# main.net
KiCad netlist of a schematic drawn in EAGLE
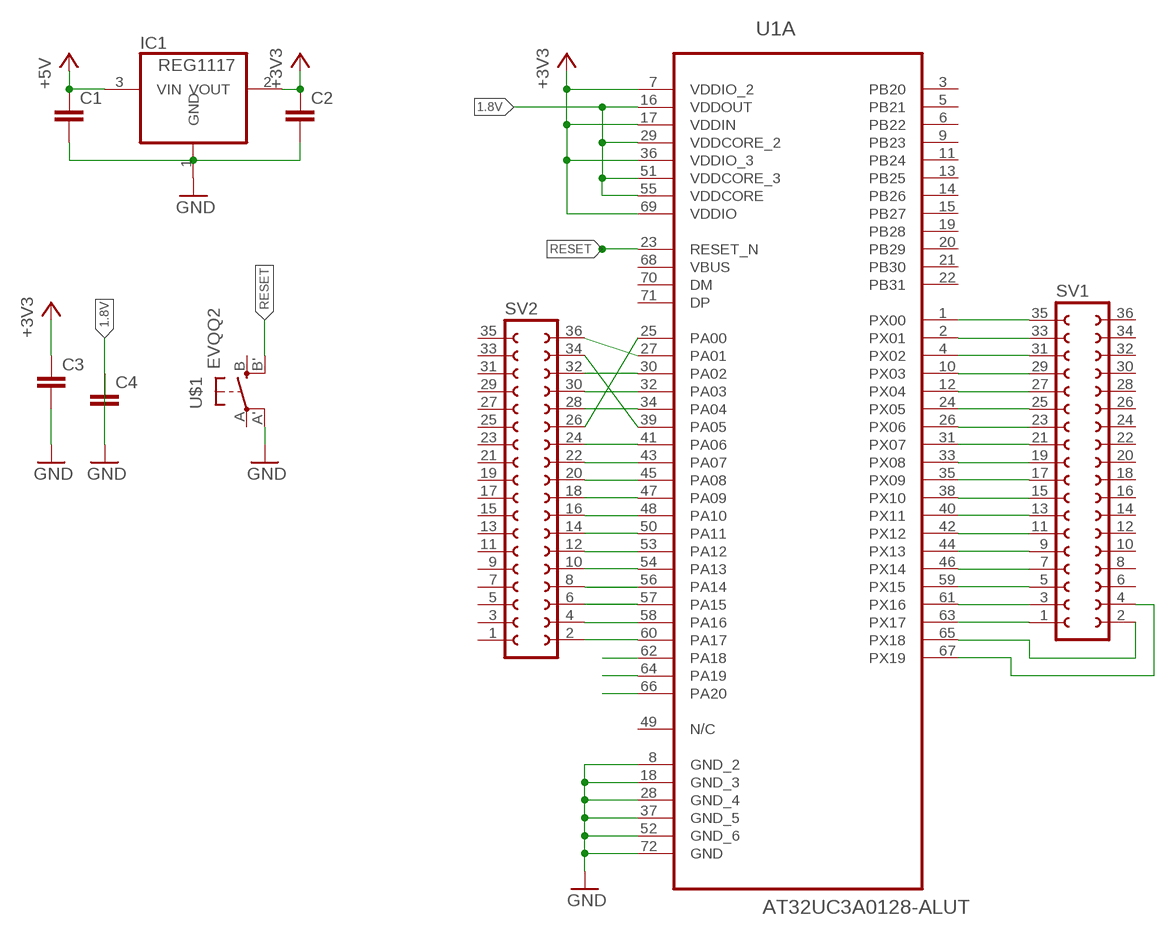
[diagram p0: schematic, sheet 1]

(export (version "E")
  (design (tool "Eeschema 10.0.6"))
  (components
    (comp (ref "C1")
      (value "C-EUC0805K")
      (footprint "eagle-import:C0805K")
      (libsource (lib "eagle-import") (part "C-EUC0805K"))
    )
    (comp (ref "C2")
      (value "C-EUC0805K")
      (footprint "eagle-import:C0805K")
      (libsource (lib "eagle-import") (part "C-EUC0805K"))
    )
    (comp (ref "C3")
      (value "C-EUC0805K")
      (footprint "eagle-import:C0805K")
      (libsource (lib "eagle-import") (part "C-EUC0805K"))
    )
    (comp (ref "C4")
      (value "C-EUC0805K")
      (footprint "eagle-import:C0805K")
      (libsource (lib "eagle-import") (part "C-EUC0805K"))
    )
    (comp (ref "IC1")
      (value "REG1117")
      (footprint "eagle-import:SOT223")
      (libsource (lib "eagle-import") (part "REG1117"))
    )
    (comp (ref "SV1")
      (value "FE18-2")
      (footprint "eagle-import:FE18-2")
      (libsource (lib "eagle-import") (part "FE18-2"))
    )
    (comp (ref "SV2")
      (value "FE18-2")
      (footprint "eagle-import:FE18-2")
      (libsource (lib "eagle-import") (part "FE18-2"))
    )
    (comp (ref "U$1")
      (value "EVQQ2")
      (footprint "eagle-import:EVQ-Q2")
      (libsource (lib "eagle-import") (part "EVQQ2"))
    )
    (comp (ref "U1")
      (value "AT32UC3A0128-ALUT")
      (footprint "eagle-import:QFP50P2200X2200X160-144N")
      (libsource (lib "eagle-import") (part "AT32UC3A0128-ALUT"))
    )
  )
  (nets
    (net (code "1") (name "+3V3") (class "Default")
      (node (ref "C2") (pin "1") (pinfunction "1_1") (pintype "passive"))
      (node (ref "C3") (pin "1") (pinfunction "1_1") (pintype "passive"))
      (node (ref "IC1") (pin "2") (pinfunction "VOUT_2") (pintype "output"))
      (node (ref "U1") (pin "17") (pinfunction "VDDIN_17") (pintype "power_in"))
      (node (ref "U1") (pin "36") (pinfunction "VDDIO_3_36") (pintype "power_in"))
      (node (ref "U1") (pin "69") (pinfunction "VDDIO_69") (pintype "power_in"))
      (node (ref "U1") (pin "7") (pinfunction "VDDIO_2_7") (pintype "power_in"))
    )
    (net (code "2") (name "+5V") (class "Default")
      (node (ref "C1") (pin "1") (pinfunction "1_1") (pintype "passive"))
      (node (ref "IC1") (pin "3") (pinfunction "VIN_3") (pintype "input"))
    )
    (net (code "3") (name "1.8V") (class "Default")
      (node (ref "C4") (pin "2") (pinfunction "2_2") (pintype "passive"))
      (node (ref "U1") (pin "16") (pinfunction "VDDOUT_16") (pintype "power_in"))
      (node (ref "U1") (pin "29") (pinfunction "VDDCORE_2_29") (pintype "power_in"))
      (node (ref "U1") (pin "51") (pinfunction "VDDCORE_3_51") (pintype "power_in"))
      (node (ref "U1") (pin "55") (pinfunction "VDDCORE_55") (pintype "power_in"))
    )
    (net (code "4") (name "GND") (class "Default")
      (node (ref "C3") (pin "2") (pinfunction "2_2") (pintype "passive"))
      (node (ref "C4") (pin "1") (pinfunction "1_1") (pintype "passive"))
      (node (ref "IC1") (pin "1") (pinfunction "GND_1") (pintype "power_in"))
      (node (ref "U$1") (pin "A'") (pinfunction "P1_A'") (pintype "passive"))
      (node (ref "U1") (pin "18") (pinfunction "GND_3_18") (pintype "passive"))
      (node (ref "U1") (pin "28") (pinfunction "GND_4_28") (pintype "passive"))
      (node (ref "U1") (pin "37") (pinfunction "GND_5_37") (pintype "passive"))
      (node (ref "U1") (pin "52") (pinfunction "GND_6_52") (pintype "passive"))
      (node (ref "U1") (pin "72") (pinfunction "GND_72") (pintype "passive"))
      (node (ref "U1") (pin "8") (pinfunction "GND_2_8") (pintype "passive"))
    )
    (net (code "5") (name "Net-(C1-Pad2)") (class "Default")
      (node (ref "C1") (pin "2") (pinfunction "2_2") (pintype "passive"))
      (node (ref "C2") (pin "2") (pinfunction "2_2") (pintype "passive"))
    )
    (net (code "6") (name "Net-(U1A-PA00)") (class "Default")
      (node (ref "SV2") (pin "26") (pinfunction "26_26") (pintype "passive"))
      (node (ref "U1") (pin "25") (pinfunction "PA00_25") (pintype "bidirectional"))
    )
    (net (code "7") (name "Net-(U1A-PA01)") (class "Default")
      (node (ref "SV2") (pin "36") (pinfunction "36_36") (pintype "passive"))
      (node (ref "U1") (pin "27") (pinfunction "PA01_27") (pintype "bidirectional"))
    )
    (net (code "8") (name "Net-(U1A-PA02)") (class "Default")
      (node (ref "SV2") (pin "32") (pinfunction "32_32") (pintype "passive"))
      (node (ref "U1") (pin "30") (pinfunction "PA02_30") (pintype "bidirectional"))
    )
    (net (code "9") (name "Net-(U1A-PA03)") (class "Default")
      (node (ref "SV2") (pin "30") (pinfunction "30_30") (pintype "passive"))
      (node (ref "U1") (pin "32") (pinfunction "PA03_32") (pintype "bidirectional"))
    )
    (net (code "10") (name "Net-(U1A-PA04)") (class "Default")
      (node (ref "SV2") (pin "28") (pinfunction "28_28") (pintype "passive"))
      (node (ref "U1") (pin "34") (pinfunction "PA04_34") (pintype "bidirectional"))
    )
    (net (code "11") (name "Net-(U1A-PA05)") (class "Default")
      (node (ref "SV2") (pin "34") (pinfunction "34_34") (pintype "passive"))
      (node (ref "U1") (pin "39") (pinfunction "PA05_39") (pintype "bidirectional"))
    )
    (net (code "12") (name "Net-(U1A-PA06)") (class "Default")
      (node (ref "SV2") (pin "24") (pinfunction "24_24") (pintype "passive"))
      (node (ref "U1") (pin "41") (pinfunction "PA06_41") (pintype "bidirectional"))
    )
    (net (code "13") (name "Net-(U1A-PA07)") (class "Default")
      (node (ref "SV2") (pin "22") (pinfunction "22_22") (pintype "passive"))
      (node (ref "U1") (pin "43") (pinfunction "PA07_43") (pintype "bidirectional"))
    )
    (net (code "14") (name "Net-(U1A-PA08)") (class "Default")
      (node (ref "SV2") (pin "20") (pinfunction "20_20") (pintype "passive"))
      (node (ref "U1") (pin "45") (pinfunction "PA08_45") (pintype "bidirectional"))
    )
    (net (code "15") (name "Net-(U1A-PA09)") (class "Default")
      (node (ref "SV2") (pin "18") (pinfunction "18_18") (pintype "passive"))
      (node (ref "U1") (pin "47") (pinfunction "PA09_47") (pintype "bidirectional"))
    )
    (net (code "16") (name "Net-(U1A-PA10)") (class "Default")
      (node (ref "SV2") (pin "16") (pinfunction "16_16") (pintype "passive"))
      (node (ref "U1") (pin "48") (pinfunction "PA10_48") (pintype "bidirectional"))
    )
    (net (code "17") (name "Net-(U1A-PA11)") (class "Default")
      (node (ref "SV2") (pin "14") (pinfunction "14_14") (pintype "passive"))
      (node (ref "U1") (pin "50") (pinfunction "PA11_50") (pintype "bidirectional"))
    )
    (net (code "18") (name "Net-(U1A-PA12)") (class "Default")
      (node (ref "SV2") (pin "12") (pinfunction "12_12") (pintype "passive"))
      (node (ref "U1") (pin "53") (pinfunction "PA12_53") (pintype "bidirectional"))
    )
    (net (code "19") (name "Net-(U1A-PA13)") (class "Default")
      (node (ref "SV2") (pin "10") (pinfunction "10_10") (pintype "passive"))
      (node (ref "U1") (pin "54") (pinfunction "PA13_54") (pintype "bidirectional"))
    )
    (net (code "20") (name "Net-(U1A-PA14)") (class "Default")
      (node (ref "SV2") (pin "8") (pinfunction "8_8") (pintype "passive"))
      (node (ref "U1") (pin "56") (pinfunction "PA14_56") (pintype "bidirectional"))
    )
    (net (code "21") (name "Net-(U1A-PA15)") (class "Default")
      (node (ref "SV2") (pin "6") (pinfunction "6_6") (pintype "passive"))
      (node (ref "U1") (pin "57") (pinfunction "PA15_57") (pintype "bidirectional"))
    )
    (net (code "22") (name "Net-(U1A-PA16)") (class "Default")
      (node (ref "SV2") (pin "4") (pinfunction "4_4") (pintype "passive"))
      (node (ref "U1") (pin "58") (pinfunction "PA16_58") (pintype "bidirectional"))
    )
    (net (code "23") (name "Net-(U1A-PA17)") (class "Default")
      (node (ref "SV2") (pin "2") (pinfunction "2_2") (pintype "passive"))
      (node (ref "U1") (pin "60") (pinfunction "PA17_60") (pintype "bidirectional"))
    )
    (net (code "24") (name "Net-(U1A-PX00)") (class "Default")
      (node (ref "SV1") (pin "35") (pinfunction "35_35") (pintype "passive"))
      (node (ref "U1") (pin "1") (pinfunction "PX00_1") (pintype "bidirectional"))
    )
    (net (code "25") (name "Net-(U1A-PX01)") (class "Default")
      (node (ref "SV1") (pin "33") (pinfunction "33_33") (pintype "passive"))
      (node (ref "U1") (pin "2") (pinfunction "PX01_2") (pintype "bidirectional"))
    )
    (net (code "26") (name "Net-(U1A-PX02)") (class "Default")
      (node (ref "SV1") (pin "31") (pinfunction "31_31") (pintype "passive"))
      (node (ref "U1") (pin "4") (pinfunction "PX02_4") (pintype "bidirectional"))
    )
    (net (code "27") (name "Net-(U1A-PX03)") (class "Default")
      (node (ref "SV1") (pin "29") (pinfunction "29_29") (pintype "passive"))
      (node (ref "U1") (pin "10") (pinfunction "PX03_10") (pintype "bidirectional"))
    )
    (net (code "28") (name "Net-(U1A-PX04)") (class "Default")
      (node (ref "SV1") (pin "27") (pinfunction "27_27") (pintype "passive"))
      (node (ref "U1") (pin "12") (pinfunction "PX04_12") (pintype "bidirectional"))
    )
    (net (code "29") (name "Net-(U1A-PX05)") (class "Default")
      (node (ref "SV1") (pin "25") (pinfunction "25_25") (pintype "passive"))
      (node (ref "U1") (pin "24") (pinfunction "PX05_24") (pintype "bidirectional"))
    )
    (net (code "30") (name "Net-(U1A-PX06)") (class "Default")
      (node (ref "SV1") (pin "23") (pinfunction "23_23") (pintype "passive"))
      (node (ref "U1") (pin "26") (pinfunction "PX06_26") (pintype "bidirectional"))
    )
    (net (code "31") (name "Net-(U1A-PX07)") (class "Default")
      (node (ref "SV1") (pin "21") (pinfunction "21_21") (pintype "passive"))
      (node (ref "U1") (pin "31") (pinfunction "PX07_31") (pintype "bidirectional"))
    )
    (net (code "32") (name "Net-(U1A-PX08)") (class "Default")
      (node (ref "SV1") (pin "19") (pinfunction "19_19") (pintype "passive"))
      (node (ref "U1") (pin "33") (pinfunction "PX08_33") (pintype "bidirectional"))
    )
    (net (code "33") (name "Net-(U1A-PX09)") (class "Default")
      (node (ref "SV1") (pin "17") (pinfunction "17_17") (pintype "passive"))
      (node (ref "U1") (pin "35") (pinfunction "PX09_35") (pintype "bidirectional"))
    )
    (net (code "34") (name "Net-(U1A-PX10)") (class "Default")
      (node (ref "SV1") (pin "15") (pinfunction "15_15") (pintype "passive"))
      (node (ref "U1") (pin "38") (pinfunction "PX10_38") (pintype "bidirectional"))
    )
    (net (code "35") (name "Net-(U1A-PX11)") (class "Default")
      (node (ref "SV1") (pin "13") (pinfunction "13_13") (pintype "passive"))
      (node (ref "U1") (pin "40") (pinfunction "PX11_40") (pintype "bidirectional"))
    )
    (net (code "36") (name "Net-(U1A-PX12)") (class "Default")
      (node (ref "SV1") (pin "11") (pinfunction "11_11") (pintype "passive"))
      (node (ref "U1") (pin "42") (pinfunction "PX12_42") (pintype "bidirectional"))
    )
    (net (code "37") (name "Net-(U1A-PX13)") (class "Default")
      (node (ref "SV1") (pin "9") (pinfunction "9_9") (pintype "passive"))
      (node (ref "U1") (pin "44") (pinfunction "PX13_44") (pintype "bidirectional"))
    )
    (net (code "38") (name "Net-(U1A-PX14)") (class "Default")
      (node (ref "SV1") (pin "7") (pinfunction "7_7") (pintype "passive"))
      (node (ref "U1") (pin "46") (pinfunction "PX14_46") (pintype "bidirectional"))
    )
    (net (code "39") (name "Net-(U1A-PX15)") (class "Default")
      (node (ref "SV1") (pin "5") (pinfunction "5_5") (pintype "passive"))
      (node (ref "U1") (pin "59") (pinfunction "PX15_59") (pintype "bidirectional"))
    )
    (net (code "40") (name "Net-(U1A-PX16)") (class "Default")
      (node (ref "SV1") (pin "3") (pinfunction "3_3") (pintype "passive"))
      (node (ref "U1") (pin "61") (pinfunction "PX16_61") (pintype "bidirectional"))
    )
    (net (code "41") (name "Net-(U1A-PX17)") (class "Default")
      (node (ref "SV1") (pin "1") (pinfunction "1_1") (pintype "passive"))
      (node (ref "U1") (pin "63") (pinfunction "PX17_63") (pintype "bidirectional"))
    )
    (net (code "42") (name "Net-(U1A-PX18)") (class "Default")
      (node (ref "SV1") (pin "2") (pinfunction "2_2") (pintype "passive"))
      (node (ref "U1") (pin "65") (pinfunction "PX18_65") (pintype "bidirectional"))
    )
    (net (code "43") (name "Net-(U1A-PX19)") (class "Default")
      (node (ref "SV1") (pin "4") (pinfunction "4_4") (pintype "passive"))
      (node (ref "U1") (pin "67") (pinfunction "PX19_67") (pintype "bidirectional"))
    )
    (net (code "44") (name "RESET") (class "Default")
      (node (ref "U$1") (pin "B'") (pinfunction "S1_B'") (pintype "passive"))
      (node (ref "U1") (pin "23") (pinfunction "RESET_N_23") (pintype "input"))
    )
    (net (code "45") (name "unconnected-(SV1-Pad6)") (class "Default")
      (node (ref "SV1") (pin "6") (pinfunction "6_6") (pintype "passive"))
    )
    (net (code "46") (name "unconnected-(SV1-Pad8)") (class "Default")
      (node (ref "SV1") (pin "8") (pinfunction "8_8") (pintype "passive"))
    )
    (net (code "47") (name "unconnected-(SV1-Pad10)") (class "Default")
      (node (ref "SV1") (pin "10") (pinfunction "10_10") (pintype "passive"))
    )
    (net (code "48") (name "unconnected-(SV1-Pad12)") (class "Default")
      (node (ref "SV1") (pin "12") (pinfunction "12_12") (pintype "passive"))
    )
    (net (code "49") (name "unconnected-(SV1-Pad14)") (class "Default")
      (node (ref "SV1") (pin "14") (pinfunction "14_14") (pintype "passive"))
    )
    (net (code "50") (name "unconnected-(SV1-Pad16)") (class "Default")
      (node (ref "SV1") (pin "16") (pinfunction "16_16") (pintype "passive"))
    )
    (net (code "51") (name "unconnected-(SV1-Pad18)") (class "Default")
      (node (ref "SV1") (pin "18") (pinfunction "18_18") (pintype "passive"))
    )
    (net (code "52") (name "unconnected-(SV1-Pad20)") (class "Default")
      (node (ref "SV1") (pin "20") (pinfunction "20_20") (pintype "passive"))
    )
    (net (code "53") (name "unconnected-(SV1-Pad22)") (class "Default")
      (node (ref "SV1") (pin "22") (pinfunction "22_22") (pintype "passive"))
    )
    (net (code "54") (name "unconnected-(SV1-Pad24)") (class "Default")
      (node (ref "SV1") (pin "24") (pinfunction "24_24") (pintype "passive"))
    )
    (net (code "55") (name "unconnected-(SV1-Pad26)") (class "Default")
      (node (ref "SV1") (pin "26") (pinfunction "26_26") (pintype "passive"))
    )
    (net (code "56") (name "unconnected-(SV1-Pad28)") (class "Default")
      (node (ref "SV1") (pin "28") (pinfunction "28_28") (pintype "passive"))
    )
    (net (code "57") (name "unconnected-(SV1-Pad30)") (class "Default")
      (node (ref "SV1") (pin "30") (pinfunction "30_30") (pintype "passive"))
    )
    (net (code "58") (name "unconnected-(SV1-Pad32)") (class "Default")
      (node (ref "SV1") (pin "32") (pinfunction "32_32") (pintype "passive"))
    )
    (net (code "59") (name "unconnected-(SV1-Pad34)") (class "Default")
      (node (ref "SV1") (pin "34") (pinfunction "34_34") (pintype "passive"))
    )
    (net (code "60") (name "unconnected-(SV1-Pad36)") (class "Default")
      (node (ref "SV1") (pin "36") (pinfunction "36_36") (pintype "passive"))
    )
    (net (code "61") (name "unconnected-(SV2-Pad1)") (class "Default")
      (node (ref "SV2") (pin "1") (pinfunction "1_1") (pintype "passive"))
    )
    (net (code "62") (name "unconnected-(SV2-Pad3)") (class "Default")
      (node (ref "SV2") (pin "3") (pinfunction "3_3") (pintype "passive"))
    )
    (net (code "63") (name "unconnected-(SV2-Pad5)") (class "Default")
      (node (ref "SV2") (pin "5") (pinfunction "5_5") (pintype "passive"))
    )
    (net (code "64") (name "unconnected-(SV2-Pad7)") (class "Default")
      (node (ref "SV2") (pin "7") (pinfunction "7_7") (pintype "passive"))
    )
    (net (code "65") (name "unconnected-(SV2-Pad9)") (class "Default")
      (node (ref "SV2") (pin "9") (pinfunction "9_9") (pintype "passive"))
    )
    (net (code "66") (name "unconnected-(SV2-Pad11)") (class "Default")
      (node (ref "SV2") (pin "11") (pinfunction "11_11") (pintype "passive"))
    )
    (net (code "67") (name "unconnected-(SV2-Pad13)") (class "Default")
      (node (ref "SV2") (pin "13") (pinfunction "13_13") (pintype "passive"))
    )
    (net (code "68") (name "unconnected-(SV2-Pad15)") (class "Default")
      (node (ref "SV2") (pin "15") (pinfunction "15_15") (pintype "passive"))
    )
    (net (code "69") (name "unconnected-(SV2-Pad17)") (class "Default")
      (node (ref "SV2") (pin "17") (pinfunction "17_17") (pintype "passive"))
    )
    (net (code "70") (name "unconnected-(SV2-Pad19)") (class "Default")
      (node (ref "SV2") (pin "19") (pinfunction "19_19") (pintype "passive"))
    )
    (net (code "71") (name "unconnected-(SV2-Pad21)") (class "Default")
      (node (ref "SV2") (pin "21") (pinfunction "21_21") (pintype "passive"))
    )
    (net (code "72") (name "unconnected-(SV2-Pad23)") (class "Default")
      (node (ref "SV2") (pin "23") (pinfunction "23_23") (pintype "passive"))
    )
    (net (code "73") (name "unconnected-(SV2-Pad25)") (class "Default")
      (node (ref "SV2") (pin "25") (pinfunction "25_25") (pintype "passive"))
    )
    (net (code "74") (name "unconnected-(SV2-Pad27)") (class "Default")
      (node (ref "SV2") (pin "27") (pinfunction "27_27") (pintype "passive"))
    )
    (net (code "75") (name "unconnected-(SV2-Pad29)") (class "Default")
      (node (ref "SV2") (pin "29") (pinfunction "29_29") (pintype "passive"))
    )
    (net (code "76") (name "unconnected-(SV2-Pad31)") (class "Default")
      (node (ref "SV2") (pin "31") (pinfunction "31_31") (pintype "passive"))
    )
    (net (code "77") (name "unconnected-(SV2-Pad33)") (class "Default")
      (node (ref "SV2") (pin "33") (pinfunction "33_33") (pintype "passive"))
    )
    (net (code "78") (name "unconnected-(SV2-Pad35)") (class "Default")
      (node (ref "SV2") (pin "35") (pinfunction "35_35") (pintype "passive"))
    )
    (net (code "79") (name "unconnected-(U$1-P-PadA)") (class "Default")
      (node (ref "U$1") (pin "A") (pinfunction "P_A") (pintype "passive"))
    )
    (net (code "80") (name "unconnected-(U$1-S-PadB)") (class "Default")
      (node (ref "U$1") (pin "B") (pinfunction "S_B") (pintype "passive"))
    )
    (net (code "81") (name "unconnected-(U1A-DM-Pad70)") (class "Default")
      (node (ref "U1") (pin "70") (pinfunction "DM_70") (pintype "input"))
    )
    (net (code "82") (name "unconnected-(U1A-DP-Pad71)") (class "Default")
      (node (ref "U1") (pin "71") (pinfunction "DP_71") (pintype "input"))
    )
    (net (code "83") (name "unconnected-(U1A-N{slash}C-Pad49)") (class "Default")
      (node (ref "U1") (pin "49") (pinfunction "N/C_49") (pintype "no_connect"))
    )
    (net (code "84") (name "unconnected-(U1A-PA18-Pad62)") (class "Default")
      (node (ref "U1") (pin "62") (pinfunction "PA18_62") (pintype "bidirectional"))
    )
    (net (code "85") (name "unconnected-(U1A-PA19-Pad64)") (class "Default")
      (node (ref "U1") (pin "64") (pinfunction "PA19_64") (pintype "bidirectional"))
    )
    (net (code "86") (name "unconnected-(U1A-PA20-Pad66)") (class "Default")
      (node (ref "U1") (pin "66") (pinfunction "PA20_66") (pintype "bidirectional"))
    )
    (net (code "87") (name "unconnected-(U1A-PB20-Pad3)") (class "Default")
      (node (ref "U1") (pin "3") (pinfunction "PB20_3") (pintype "bidirectional"))
    )
    (net (code "88") (name "unconnected-(U1A-PB21-Pad5)") (class "Default")
      (node (ref "U1") (pin "5") (pinfunction "PB21_5") (pintype "bidirectional"))
    )
    (net (code "89") (name "unconnected-(U1A-PB22-Pad6)") (class "Default")
      (node (ref "U1") (pin "6") (pinfunction "PB22_6") (pintype "bidirectional"))
    )
    (net (code "90") (name "unconnected-(U1A-PB23-Pad9)") (class "Default")
      (node (ref "U1") (pin "9") (pinfunction "PB23_9") (pintype "bidirectional"))
    )
    (net (code "91") (name "unconnected-(U1A-PB24-Pad11)") (class "Default")
      (node (ref "U1") (pin "11") (pinfunction "PB24_11") (pintype "bidirectional"))
    )
    (net (code "92") (name "unconnected-(U1A-PB25-Pad13)") (class "Default")
      (node (ref "U1") (pin "13") (pinfunction "PB25_13") (pintype "bidirectional"))
    )
    (net (code "93") (name "unconnected-(U1A-PB26-Pad14)") (class "Default")
      (node (ref "U1") (pin "14") (pinfunction "PB26_14") (pintype "bidirectional"))
    )
    (net (code "94") (name "unconnected-(U1A-PB27-Pad15)") (class "Default")
      (node (ref "U1") (pin "15") (pinfunction "PB27_15") (pintype "bidirectional"))
    )
    (net (code "95") (name "unconnected-(U1A-PB28-Pad19)") (class "Default")
      (node (ref "U1") (pin "19") (pinfunction "PB28_19") (pintype "bidirectional"))
    )
    (net (code "96") (name "unconnected-(U1A-PB29-Pad20)") (class "Default")
      (node (ref "U1") (pin "20") (pinfunction "PB29_20") (pintype "bidirectional"))
    )
    (net (code "97") (name "unconnected-(U1A-PB30-Pad21)") (class "Default")
      (node (ref "U1") (pin "21") (pinfunction "PB30_21") (pintype "bidirectional"))
    )
    (net (code "98") (name "unconnected-(U1A-PB31-Pad22)") (class "Default")
      (node (ref "U1") (pin "22") (pinfunction "PB31_22") (pintype "bidirectional"))
    )
    (net (code "99") (name "unconnected-(U1A-VBUS-Pad68)") (class "Default")
      (node (ref "U1") (pin "68") (pinfunction "VBUS_68") (pintype "input"))
    )
  )
)
